# Adafruit_Breadboard_NeoPixel.net
KiCad netlist of a schematic drawn in EAGLE
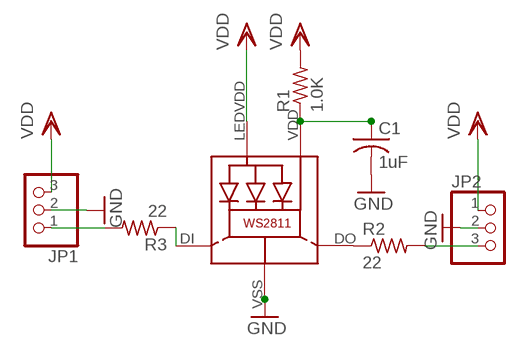
[diagram p0: schematic, sheet 1]

(export (version "E")
  (design (tool "Eeschema 10.0.6"))
  (components
    (comp (ref "C1")
      (value "1uF")
      (footprint "eagle-import:C0603K")
      (libsource (lib "eagle-import") (part "C-USC0603K"))
    )
    (comp (ref "JP1")
      (value "PINHD-1X3CB")
      (footprint "eagle-import:1X03-CLEANBIG")
      (libsource (lib "eagle-import") (part "PINHD-1X3CB"))
    )
    (comp (ref "JP2")
      (value "PINHD-1X3CB")
      (footprint "eagle-import:1X03-CLEANBIG")
      (libsource (lib "eagle-import") (part "PINHD-1X3CB"))
    )
    (comp (ref "LED1")
      (value "WS28115050")
      (footprint "eagle-import:WS28115050")
      (libsource (lib "eagle-import") (part "WS28115050"))
    )
    (comp (ref "R1")
      (value "1.0K")
      (footprint "eagle-import:R0603")
      (libsource (lib "eagle-import") (part "R-US_R0603"))
    )
    (comp (ref "R2")
      (value "22")
      (footprint "eagle-import:R0603")
      (libsource (lib "eagle-import") (part "R-US_R0603"))
    )
    (comp (ref "R3")
      (value "22")
      (footprint "eagle-import:R0603")
      (libsource (lib "eagle-import") (part "R-US_R0603"))
    )
  )
  (nets
    (net (code "1") (name "GND") (class "Default")
      (node (ref "C1") (pin "2") (pinfunction "2_2") (pintype "passive"))
      (node (ref "JP1") (pin "2") (pinfunction "2_2") (pintype "passive"))
      (node (ref "JP2") (pin "2") (pinfunction "2_2") (pintype "passive"))
      (node (ref "LED1") (pin "VSS") (pinfunction "GND_VSS") (pintype "power_in"))
    )
    (net (code "2") (name "Net-(C1-Pad1)") (class "Default")
      (node (ref "C1") (pin "1") (pinfunction "1_1") (pintype "passive"))
      (node (ref "LED1") (pin "VDD") (pinfunction "VDD_VDD") (pintype "power_in"))
      (node (ref "R1") (pin "1") (pinfunction "1_1") (pintype "passive"))
    )
    (net (code "3") (name "Net-(JP1-Pad1)") (class "Default")
      (node (ref "JP1") (pin "1") (pinfunction "1_1") (pintype "passive"))
      (node (ref "R3") (pin "2") (pinfunction "2_2") (pintype "passive"))
    )
    (net (code "4") (name "Net-(JP2-Pad3)") (class "Default")
      (node (ref "JP2") (pin "3") (pinfunction "3_3") (pintype "passive"))
      (node (ref "R2") (pin "2") (pinfunction "2_2") (pintype "passive"))
    )
    (net (code "5") (name "Net-(LED1-PadDI)") (class "Default")
      (node (ref "LED1") (pin "DI") (pinfunction "DI_DI") (pintype "input"))
      (node (ref "R3") (pin "1") (pinfunction "1_1") (pintype "passive"))
    )
    (net (code "6") (name "Net-(LED1-PadDO)") (class "Default")
      (node (ref "LED1") (pin "DO") (pinfunction "DO_DO") (pintype "output"))
      (node (ref "R2") (pin "1") (pinfunction "1_1") (pintype "passive"))
    )
    (net (code "7") (name "VDD") (class "Default")
      (node (ref "JP1") (pin "3") (pinfunction "3_3") (pintype "passive"))
      (node (ref "JP2") (pin "1") (pinfunction "1_1") (pintype "passive"))
      (node (ref "LED1") (pin "LEDVDD") (pinfunction "LEDVDD_LEDVDD") (pintype "power_in"))
      (node (ref "R1") (pin "2") (pinfunction "2_2") (pintype "passive"))
    )
  )
)
